# driver-ha-v2.net
KiCad netlist of a schematic drawn in EAGLE
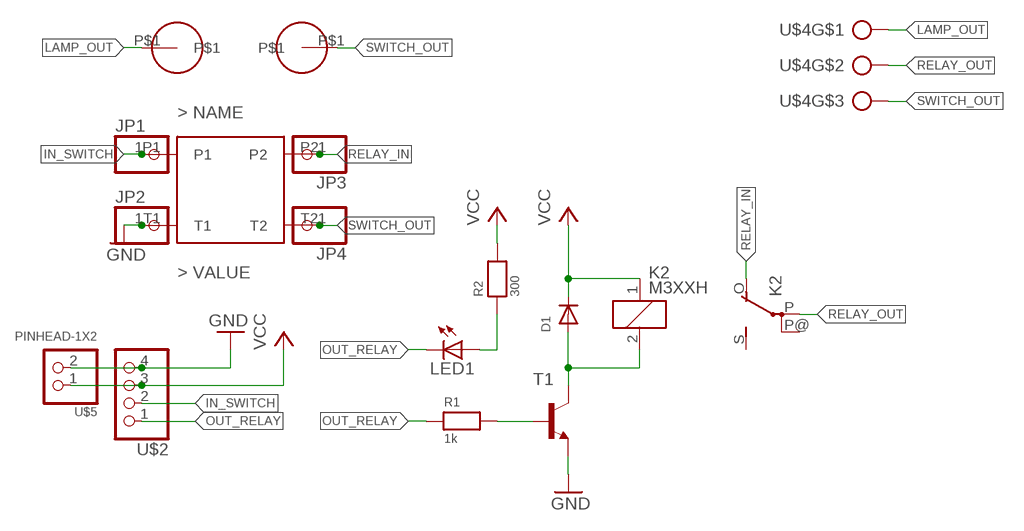
[diagram p0: schematic, sheet 1]

(export (version "E")
  (design (tool "Eeschema 10.0.6"))
  (components
    (comp (ref "D1")
      (value "DIODESMA")
      (footprint "eagle-import:SMADIODE")
      (libsource (lib "eagle-import") (part "DIODESMA"))
    )
    (comp (ref "JP1")
      (value "PINHD-1X1")
      (footprint "eagle-import:1X01")
      (libsource (lib "eagle-import") (part "PINHD-1X1"))
    )
    (comp (ref "JP2")
      (value "PINHD-1X1")
      (footprint "eagle-import:1X01")
      (libsource (lib "eagle-import") (part "PINHD-1X1"))
    )
    (comp (ref "JP3")
      (value "PINHD-1X1")
      (footprint "eagle-import:1X01")
      (libsource (lib "eagle-import") (part "PINHD-1X1"))
    )
    (comp (ref "JP4")
      (value "PINHD-1X1")
      (footprint "eagle-import:1X01")
      (libsource (lib "eagle-import") (part "PINHD-1X1"))
    )
    (comp (ref "K2")
      (value "M3XXH")
      (footprint "eagle-import:M3XXH")
      (libsource (lib "eagle-import") (part "M3XXH"))
    )
    (comp (ref "LED1")
      (value "LEDCHIPLED_0805")
      (footprint "eagle-import:CHIPLED_0805")
      (libsource (lib "eagle-import") (part "LEDCHIPLED_0805"))
    )
    (comp (ref "R1")
      (value "1k")
      (footprint "eagle-import:0603")
      (libsource (lib "eagle-import") (part "RESISTOR0603"))
    )
    (comp (ref "R2")
      (value "300")
      (footprint "eagle-import:0603")
      (libsource (lib "eagle-import") (part "RESISTOR0603"))
    )
    (comp (ref "ROOM_SWITCH")
      (value "DPST-SWITCH-1221")
      (footprint "eagle-import:TOGGLE-SW-E1221")
      (libsource (lib "eagle-import") (part "DPST-SWITCH-1221"))
    )
    (comp (ref "T1")
      (value "MMBT2222ALT1-NPN-SOT23-BEC")
      (footprint "eagle-import:SOT23-BEC")
      (libsource (lib "eagle-import") (part "-NPN-SOT23-BECMMBT2222ALT1"))
    )
    (comp (ref "U$1")
      (value "CONN-CABLE")
      (footprint "eagle-import:CONN-CABLE")
      (libsource (lib "eagle-import") (part "CONN-CABLE"))
    )
    (comp (ref "U$2")
      (value "HEADER-1X4")
      (footprint "eagle-import:1X04_OVAL")
      (libsource (lib "eagle-import") (part "HEADER-1X4"))
    )
    (comp (ref "U$3")
      (value "CONN-CABLE")
      (footprint "eagle-import:CONN-CABLE")
      (libsource (lib "eagle-import") (part "CONN-CABLE"))
    )
    (comp (ref "U$4")
      (value "AK3003")
      (footprint "eagle-import:AK3003")
      (libsource (lib "eagle-import") (part "AK3003"))
    )
    (comp (ref "U$5")
      (value "PINHEAD-1X2")
      (footprint "eagle-import:PIHEAD-1X2")
      (libsource (lib "eagle-import") (part "PINHEAD-1X2"))
    )
  )
  (nets
    (net (code "1") (name "GND") (class "Default")
      (node (ref "JP2") (pin "1") (pinfunction "1_1") (pintype "passive"))
      (node (ref "ROOM_SWITCH") (pin "T1") (pinfunction "T1_T1") (pintype "bidirectional"))
      (node (ref "T1") (pin "E") (pinfunction "E_E") (pintype "passive"))
      (node (ref "U$2") (pin "4") (pinfunction "4_4") (pintype "passive"))
      (node (ref "U$5") (pin "2") (pinfunction "2_2") (pintype "passive"))
    )
    (net (code "2") (name "IN_SWITCH") (class "Default")
      (node (ref "JP1") (pin "1") (pinfunction "1_1") (pintype "passive"))
      (node (ref "ROOM_SWITCH") (pin "P1") (pinfunction "P1_P1") (pintype "bidirectional"))
      (node (ref "U$2") (pin "2") (pinfunction "2_2") (pintype "passive"))
    )
    (net (code "3") (name "LAMP_OUT") (class "Default")
      (node (ref "U$1") (pin "P$1") (pinfunction "P$1_P$1") (pintype "bidirectional"))
      (node (ref "U$4") (pin "1") (pinfunction "KL_1") (pintype "passive"))
    )
    (net (code "4") (name "Net-(D1-PadA)") (class "Default")
      (node (ref "D1") (pin "A") (pinfunction "A_A") (pintype "passive"))
      (node (ref "K2") (pin "2") (pinfunction "2_2") (pintype "passive"))
      (node (ref "T1") (pin "C") (pinfunction "C_C") (pintype "passive"))
    )
    (net (code "5") (name "Net-(LED1-PadA)") (class "Default")
      (node (ref "LED1") (pin "A") (pinfunction "A_A") (pintype "passive"))
      (node (ref "R2") (pin "1") (pinfunction "1_1") (pintype "passive"))
    )
    (net (code "6") (name "Net-(R1-Pad2)") (class "Default")
      (node (ref "R1") (pin "2") (pinfunction "2_2") (pintype "passive"))
      (node (ref "T1") (pin "B") (pinfunction "B_B") (pintype "passive"))
    )
    (net (code "7") (name "OUT_RELAY") (class "Default")
      (node (ref "LED1") (pin "C") (pinfunction "C_C") (pintype "passive"))
      (node (ref "R1") (pin "1") (pinfunction "1_1") (pintype "passive"))
      (node (ref "U$2") (pin "1") (pinfunction "1_1") (pintype "passive"))
    )
    (net (code "8") (name "RELAY_IN") (class "Default")
      (node (ref "JP3") (pin "1") (pinfunction "1_1") (pintype "passive"))
      (node (ref "K2") (pin "O") (pinfunction "O_O") (pintype "passive"))
      (node (ref "ROOM_SWITCH") (pin "P2") (pinfunction "P2_P2") (pintype "bidirectional"))
    )
    (net (code "9") (name "RELAY_OUT") (class "Default")
      (node (ref "K2") (pin "P") (pinfunction "P_P") (pintype "passive"))
      (node (ref "U$4") (pin "2") (pinfunction "KL_2") (pintype "passive"))
    )
    (net (code "10") (name "SWITCH_OUT") (class "Default")
      (node (ref "JP4") (pin "1") (pinfunction "1_1") (pintype "passive"))
      (node (ref "ROOM_SWITCH") (pin "T2") (pinfunction "T2_T2") (pintype "bidirectional"))
      (node (ref "U$3") (pin "P$1") (pinfunction "P$1_P$1") (pintype "bidirectional"))
      (node (ref "U$4") (pin "3") (pinfunction "KL_3") (pintype "passive"))
    )
    (net (code "11") (name "VCC") (class "Default")
      (node (ref "D1") (pin "C") (pinfunction "C_C") (pintype "passive"))
      (node (ref "K2") (pin "1") (pinfunction "1_1") (pintype "passive"))
      (node (ref "R2") (pin "2") (pinfunction "2_2") (pintype "passive"))
      (node (ref "U$2") (pin "3") (pinfunction "3_3") (pintype "passive"))
      (node (ref "U$5") (pin "1") (pinfunction "1_1") (pintype "passive"))
    )
    (net (code "12") (name "unconnected-(K2-PadS)") (class "Default")
      (node (ref "K2") (pin "S") (pinfunction "S_S") (pintype "passive"))
    )
    (net (code "13") (name "unconnected-(K2B-P-PadP@)") (class "Default")
      (node (ref "K2") (pin "P@") (pinfunction "P_P@") (pintype "passive"))
    )
  )
)
